# DS1624S_termometr_minibord.net
KiCad netlist of a schematic drawn in EAGLE
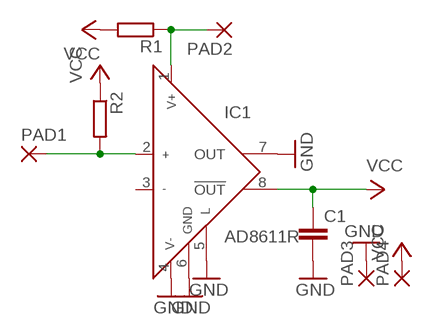
[diagram p0: schematic, sheet 1]

(export (version "E")
  (design (tool "Eeschema 10.0.6"))
  (components
    (comp (ref "C1")
      (value "C-EUC0805")
      (footprint "eagle-import:C0805")
      (libsource (lib "eagle-import") (part "C-EUC0805"))
    )
    (comp (ref "IC1")
      (value "AD8611R")
      (footprint "eagle-import:SO8")
      (fields (field (name "MPN") "AD8611ARMZ-R2"))
      (libsource (lib "eagle-import") (part "AD8611R"))
    )
    (comp (ref "PAD1")
      (value "1,6/0,8")
      (footprint "eagle-import:1,6_0,8")
      (libsource (lib "eagle-import") (part "1,6/0,8"))
    )
    (comp (ref "PAD2")
      (value "1,6/0,8")
      (footprint "eagle-import:1,6_0,8")
      (libsource (lib "eagle-import") (part "1,6/0,8"))
    )
    (comp (ref "PAD3")
      (value "1,6/0,8")
      (footprint "eagle-import:1,6_0,8")
      (libsource (lib "eagle-import") (part "1,6/0,8"))
    )
    (comp (ref "PAD4")
      (value "1,6/0,8")
      (footprint "eagle-import:1,6_0,8")
      (libsource (lib "eagle-import") (part "1,6/0,8"))
    )
    (comp (ref "R1")
      (value "R-EU_M0805")
      (footprint "eagle-import:M0805")
      (libsource (lib "eagle-import") (part "R-EU_M0805"))
    )
    (comp (ref "R2")
      (value "R-EU_M0805")
      (footprint "eagle-import:M0805")
      (libsource (lib "eagle-import") (part "R-EU_M0805"))
    )
  )
  (nets
    (net (code "1") (name "GND") (class "Default")
      (node (ref "C1") (pin "2") (pinfunction "2_2") (pintype "passive"))
      (node (ref "IC1") (pin "4") (pinfunction "V-_4") (pintype "power_in"))
      (node (ref "IC1") (pin "5") (pinfunction "L_5") (pintype "input"))
      (node (ref "IC1") (pin "6") (pinfunction "GND_6") (pintype "power_in"))
      (node (ref "IC1") (pin "7") (pinfunction "OUT_7") (pintype "output"))
      (node (ref "PAD3") (pin "1") (pinfunction "P_1") (pintype "passive"))
    )
    (net (code "2") (name "Net-(IC1-IN+)") (class "Default")
      (node (ref "IC1") (pin "2") (pinfunction "IN+_2") (pintype "input"))
      (node (ref "PAD1") (pin "1") (pinfunction "P_1") (pintype "passive"))
      (node (ref "R2") (pin "2") (pinfunction "2_2") (pintype "passive"))
    )
    (net (code "3") (name "Net-(IC1-V+)") (class "Default")
      (node (ref "IC1") (pin "1") (pinfunction "V+_1") (pintype "power_in"))
      (node (ref "PAD2") (pin "1") (pinfunction "P_1") (pintype "passive"))
      (node (ref "R1") (pin "1") (pinfunction "1_1") (pintype "passive"))
    )
    (net (code "4") (name "VCC") (class "Default")
      (node (ref "C1") (pin "1") (pinfunction "1_1") (pintype "passive"))
      (node (ref "IC1") (pin "8") (pinfunction "~{OUT}_8") (pintype "output"))
      (node (ref "PAD4") (pin "1") (pinfunction "P_1") (pintype "passive"))
      (node (ref "R1") (pin "2") (pinfunction "2_2") (pintype "passive"))
      (node (ref "R2") (pin "1") (pinfunction "1_1") (pintype "passive"))
    )
    (net (code "5") (name "unconnected-(IC1-IN--Pad3)") (class "Default")
      (node (ref "IC1") (pin "3") (pinfunction "IN-_3") (pintype "input"))
    )
  )
)
